# shield.net
KiCad netlist of a schematic drawn in EAGLE
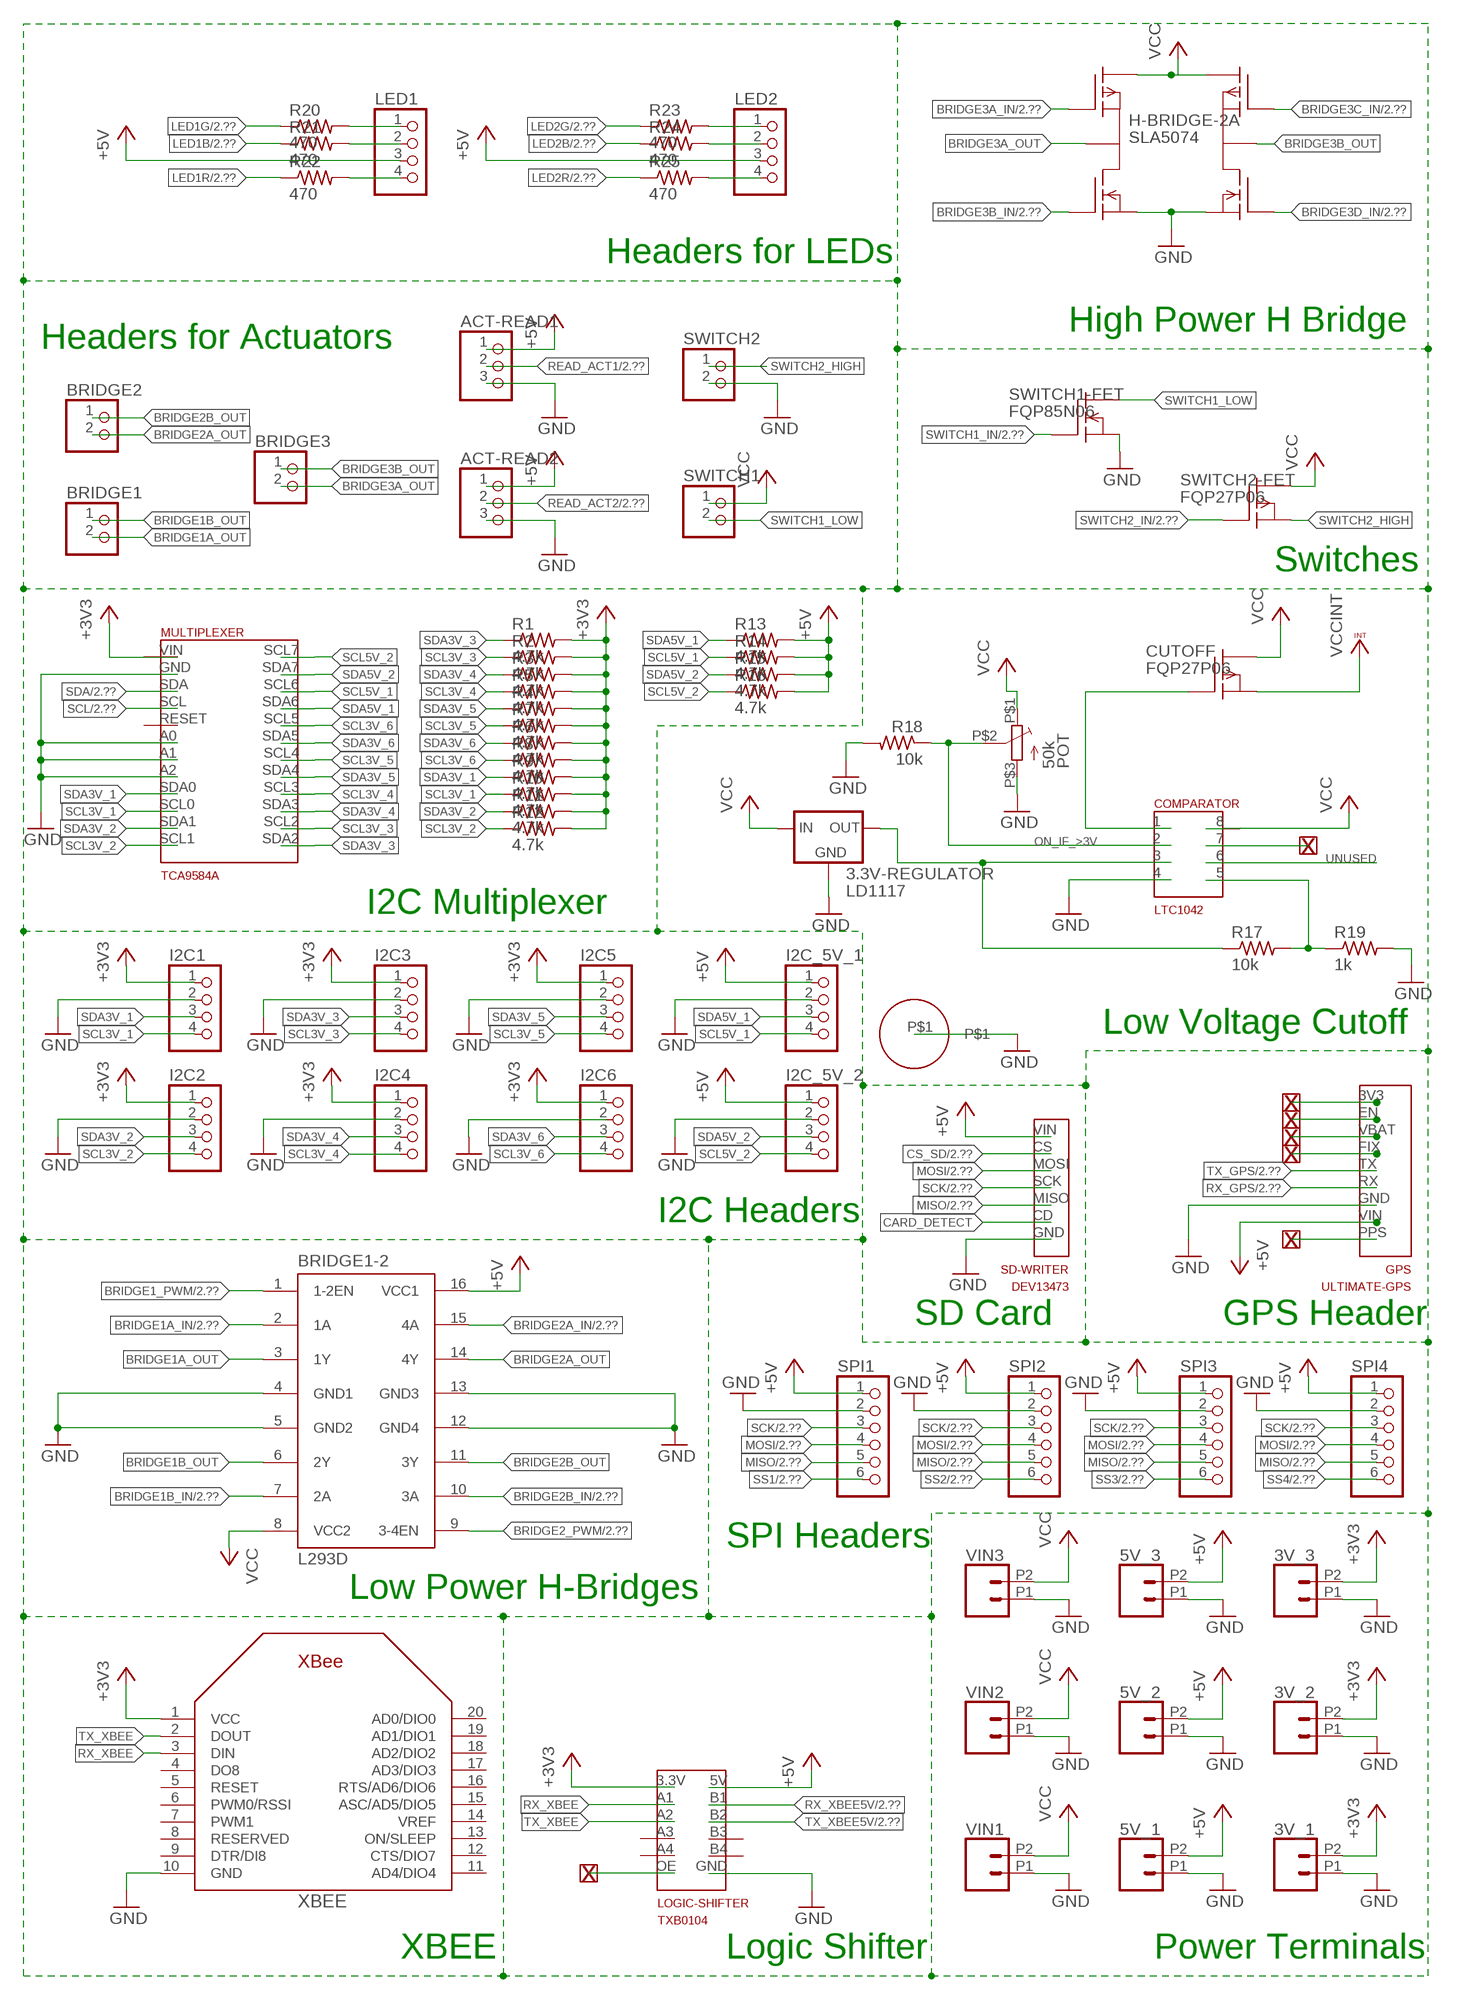
[diagram p0: schematic, sheet 1]
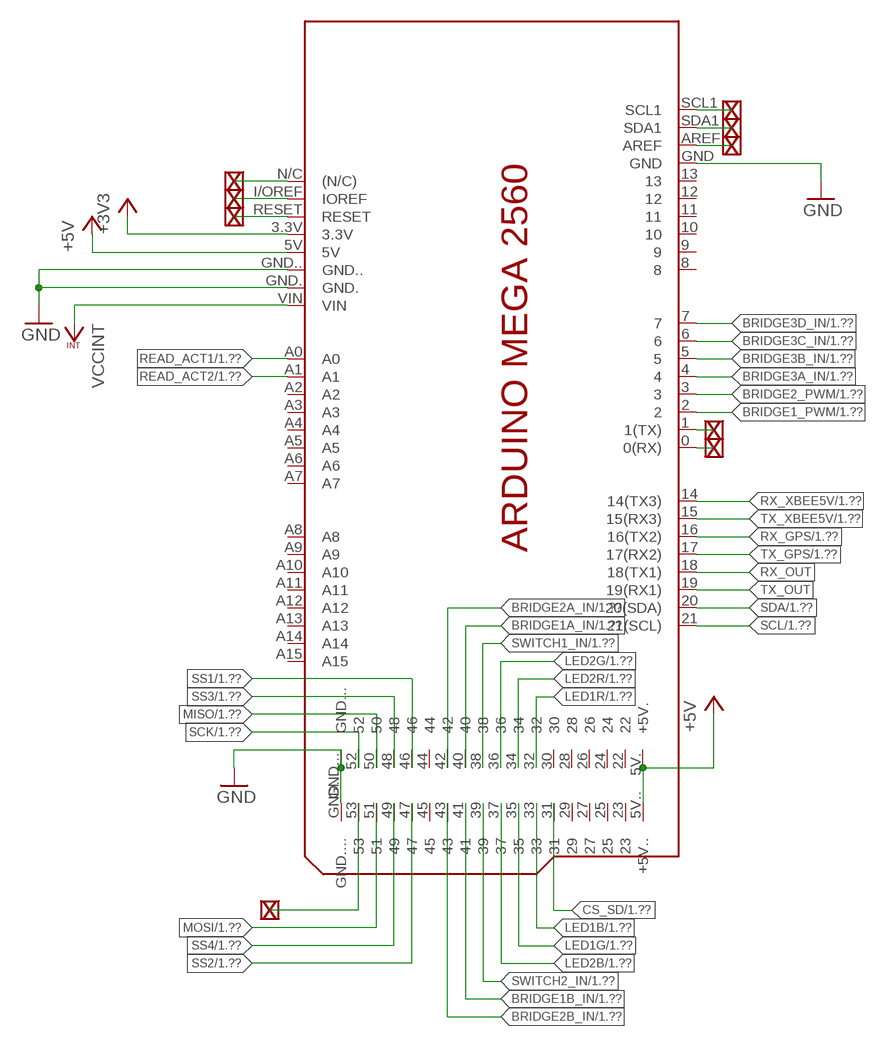
[diagram p1: schematic, sheet 2]

(export (version "E")
  (design (tool "Eeschema 10.0.6"))
  (components
    (comp (ref "PCB2")
      (value "ARDUINO_MEGA2560_SHIELD")
      (footprint "eagle-import:ARDUINO_MEGA2560_SHIELD")
      (libsource (lib "eagle-import") (part "ARDUINO_MEGA2560_SHIELD"))
    )
    (comp (ref "3.3V-REGULATOR")
      (value "LD1117")
      (footprint "eagle-import:REGULATOR")
      (libsource (lib "eagle-import") (part "LD1117"))
    )
    (comp (ref "3V_1")
      (value "CONN_022.54MM_SCREWTERM")
      (footprint "eagle-import:1X02_2.54_SCREWTERM")
      (libsource (lib "eagle-import") (part "CONN_022.54MM_SCREWTERM"))
    )
    (comp (ref "3V_2")
      (value "CONN_022.54MM_SCREWTERM")
      (footprint "eagle-import:1X02_2.54_SCREWTERM")
      (libsource (lib "eagle-import") (part "CONN_022.54MM_SCREWTERM"))
    )
    (comp (ref "3V_3")
      (value "CONN_022.54MM_SCREWTERM")
      (footprint "eagle-import:1X02_2.54_SCREWTERM")
      (libsource (lib "eagle-import") (part "CONN_022.54MM_SCREWTERM"))
    )
    (comp (ref "5V_1")
      (value "CONN_022.54MM_SCREWTERM")
      (footprint "eagle-import:1X02_2.54_SCREWTERM")
      (libsource (lib "eagle-import") (part "CONN_022.54MM_SCREWTERM"))
    )
    (comp (ref "5V_2")
      (value "CONN_022.54MM_SCREWTERM")
      (footprint "eagle-import:1X02_2.54_SCREWTERM")
      (libsource (lib "eagle-import") (part "CONN_022.54MM_SCREWTERM"))
    )
    (comp (ref "5V_3")
      (value "CONN_022.54MM_SCREWTERM")
      (footprint "eagle-import:1X02_2.54_SCREWTERM")
      (libsource (lib "eagle-import") (part "CONN_022.54MM_SCREWTERM"))
    )
    (comp (ref "ACT-READ1")
      (value "PINHD-1X3")
      (footprint "eagle-import:1X03")
      (libsource (lib "eagle-import") (part "PINHD-1X3"))
    )
    (comp (ref "ACT-READ2")
      (value "PINHD-1X3")
      (footprint "eagle-import:1X03")
      (libsource (lib "eagle-import") (part "PINHD-1X3"))
    )
    (comp (ref "BRIDGE1")
      (value "PINHD-1X2")
      (footprint "eagle-import:1X02")
      (libsource (lib "eagle-import") (part "PINHD-1X2"))
    )
    (comp (ref "BRIDGE1-2")
      (value "L293D")
      (footprint "eagle-import:DIL16")
      (libsource (lib "eagle-import") (part "L293D"))
    )
    (comp (ref "BRIDGE2")
      (value "PINHD-1X2")
      (footprint "eagle-import:1X02")
      (libsource (lib "eagle-import") (part "PINHD-1X2"))
    )
    (comp (ref "BRIDGE3")
      (value "PINHD-1X2")
      (footprint "eagle-import:1X02")
      (libsource (lib "eagle-import") (part "PINHD-1X2"))
    )
    (comp (ref "COMPARATOR")
      (value "LTC1042")
      (footprint "eagle-import:DIP8")
      (libsource (lib "eagle-import") (part "LTC1042"))
    )
    (comp (ref "CUTOFF")
      (value "FQP27P06")
      (footprint "eagle-import:MOSFET")
      (libsource (lib "eagle-import") (part "FQP27P06"))
    )
    (comp (ref "GPS")
      (value "ULTIMATE-GPS")
      (footprint "eagle-import:GPS")
      (libsource (lib "eagle-import") (part "ULTIMATE-GPS"))
    )
    (comp (ref "H-BRIDGE-2A")
      (value "SLA5074")
      (footprint "eagle-import:SANKEN")
      (libsource (lib "eagle-import") (part "SLA5074"))
    )
    (comp (ref "I2C1")
      (value "PINHD-1X4")
      (footprint "eagle-import:1X04")
      (libsource (lib "eagle-import") (part "PINHD-1X4"))
    )
    (comp (ref "I2C2")
      (value "PINHD-1X4")
      (footprint "eagle-import:1X04")
      (libsource (lib "eagle-import") (part "PINHD-1X4"))
    )
    (comp (ref "I2C3")
      (value "PINHD-1X4")
      (footprint "eagle-import:1X04")
      (libsource (lib "eagle-import") (part "PINHD-1X4"))
    )
    (comp (ref "I2C4")
      (value "PINHD-1X4")
      (footprint "eagle-import:1X04")
      (libsource (lib "eagle-import") (part "PINHD-1X4"))
    )
    (comp (ref "I2C5")
      (value "PINHD-1X4")
      (footprint "eagle-import:1X04")
      (libsource (lib "eagle-import") (part "PINHD-1X4"))
    )
    (comp (ref "I2C6")
      (value "PINHD-1X4")
      (footprint "eagle-import:1X04")
      (libsource (lib "eagle-import") (part "PINHD-1X4"))
    )
    (comp (ref "I2C_5V_1")
      (value "PINHD-1X4")
      (footprint "eagle-import:1X04")
      (libsource (lib "eagle-import") (part "PINHD-1X4"))
    )
    (comp (ref "I2C_5V_2")
      (value "PINHD-1X4")
      (footprint "eagle-import:1X04")
      (libsource (lib "eagle-import") (part "PINHD-1X4"))
    )
    (comp (ref "LED1")
      (value "PINHD-1X4")
      (footprint "eagle-import:1X04")
      (libsource (lib "eagle-import") (part "PINHD-1X4"))
    )
    (comp (ref "LED2")
      (value "PINHD-1X4")
      (footprint "eagle-import:1X04")
      (libsource (lib "eagle-import") (part "PINHD-1X4"))
    )
    (comp (ref "LOGIC-SHIFTER")
      (value "TXB0104")
      (footprint "eagle-import:TXB0104")
      (libsource (lib "eagle-import") (part "TXB0104"))
    )
    (comp (ref "MULTIPLEXER")
      (value "TCA9584A")
      (footprint "eagle-import:TCA9584A")
      (libsource (lib "eagle-import") (part "TCA9584A"))
    )
    (comp (ref "POT")
      (value "50k")
      (footprint "eagle-import:PV37W503C01B00")
      (libsource (lib "eagle-import") (part "PV37W503C01B00"))
    )
    (comp (ref "R1")
      (value "4.7k")
      (footprint "eagle-import:0805-THM")
      (libsource (lib "eagle-import") (part "R-US_FLIPFLOP"))
    )
    (comp (ref "R2")
      (value "4.7k")
      (footprint "eagle-import:0805-THM")
      (libsource (lib "eagle-import") (part "R-US_FLIPFLOP"))
    )
    (comp (ref "R3")
      (value "4.7k")
      (footprint "eagle-import:0805-THM")
      (libsource (lib "eagle-import") (part "R-US_FLIPFLOP"))
    )
    (comp (ref "R4")
      (value "4.7k")
      (footprint "eagle-import:0805-THM")
      (libsource (lib "eagle-import") (part "R-US_FLIPFLOP"))
    )
    (comp (ref "R5")
      (value "4.7k")
      (footprint "eagle-import:0805-THM")
      (libsource (lib "eagle-import") (part "R-US_FLIPFLOP"))
    )
    (comp (ref "R6")
      (value "4.7k")
      (footprint "eagle-import:0805-THM")
      (libsource (lib "eagle-import") (part "R-US_FLIPFLOP"))
    )
    (comp (ref "R7")
      (value "4.7k")
      (footprint "eagle-import:0805-THM")
      (libsource (lib "eagle-import") (part "R-US_FLIPFLOP"))
    )
    (comp (ref "R8")
      (value "4.7k")
      (footprint "eagle-import:0805-THM")
      (libsource (lib "eagle-import") (part "R-US_FLIPFLOP"))
    )
    (comp (ref "R9")
      (value "4.7k")
      (footprint "eagle-import:0805-THM")
      (libsource (lib "eagle-import") (part "R-US_FLIPFLOP"))
    )
    (comp (ref "R10")
      (value "4.7k")
      (footprint "eagle-import:0805-THM")
      (libsource (lib "eagle-import") (part "R-US_FLIPFLOP"))
    )
    (comp (ref "R11")
      (value "4.7k")
      (footprint "eagle-import:0805-THM")
      (libsource (lib "eagle-import") (part "R-US_FLIPFLOP"))
    )
    (comp (ref "R12")
      (value "4.7k")
      (footprint "eagle-import:0805-THM")
      (libsource (lib "eagle-import") (part "R-US_FLIPFLOP"))
    )
    (comp (ref "R13")
      (value "4.7k")
      (footprint "eagle-import:0805-THM")
      (libsource (lib "eagle-import") (part "R-US_FLIPFLOP"))
    )
    (comp (ref "R14")
      (value "4.7k")
      (footprint "eagle-import:0805-THM")
      (libsource (lib "eagle-import") (part "R-US_FLIPFLOP"))
    )
    (comp (ref "R15")
      (value "4.7k")
      (footprint "eagle-import:0805-THM")
      (libsource (lib "eagle-import") (part "R-US_FLIPFLOP"))
    )
    (comp (ref "R16")
      (value "4.7k")
      (footprint "eagle-import:0805-THM")
      (libsource (lib "eagle-import") (part "R-US_FLIPFLOP"))
    )
    (comp (ref "R17")
      (value "10k")
      (footprint "eagle-import:0805-THM")
      (libsource (lib "eagle-import") (part "R-US_FLIPFLOP"))
    )
    (comp (ref "R18")
      (value "10k")
      (footprint "eagle-import:0805-THM")
      (libsource (lib "eagle-import") (part "R-US_FLIPFLOP"))
    )
    (comp (ref "R19")
      (value "1k")
      (footprint "eagle-import:0805-THM")
      (libsource (lib "eagle-import") (part "R-US_FLIPFLOP"))
    )
    (comp (ref "R20")
      (value "470")
      (footprint "eagle-import:0805-THM")
      (libsource (lib "eagle-import") (part "R-US_FLIPFLOP"))
    )
    (comp (ref "R21")
      (value "470")
      (footprint "eagle-import:0805-THM")
      (libsource (lib "eagle-import") (part "R-US_FLIPFLOP"))
    )
    (comp (ref "R22")
      (value "470")
      (footprint "eagle-import:0805-THM")
      (libsource (lib "eagle-import") (part "R-US_FLIPFLOP"))
    )
    (comp (ref "R23")
      (value "470")
      (footprint "eagle-import:0805-THM")
      (libsource (lib "eagle-import") (part "R-US_FLIPFLOP"))
    )
    (comp (ref "R24")
      (value "470")
      (footprint "eagle-import:0805-THM")
      (libsource (lib "eagle-import") (part "R-US_FLIPFLOP"))
    )
    (comp (ref "R25")
      (value "470")
      (footprint "eagle-import:0805-THM")
      (libsource (lib "eagle-import") (part "R-US_FLIPFLOP"))
    )
    (comp (ref "SD-WRITER")
      (value "DEV13473")
      (footprint "eagle-import:DEV13743")
      (libsource (lib "eagle-import") (part "DEV13473"))
    )
    (comp (ref "SPI1")
      (value "PINHD-1X6")
      (footprint "eagle-import:1X06")
      (libsource (lib "eagle-import") (part "PINHD-1X6"))
    )
    (comp (ref "SPI2")
      (value "PINHD-1X6")
      (footprint "eagle-import:1X06")
      (libsource (lib "eagle-import") (part "PINHD-1X6"))
    )
    (comp (ref "SPI3")
      (value "PINHD-1X6")
      (footprint "eagle-import:1X06")
      (libsource (lib "eagle-import") (part "PINHD-1X6"))
    )
    (comp (ref "SPI4")
      (value "PINHD-1X6")
      (footprint "eagle-import:1X06")
      (libsource (lib "eagle-import") (part "PINHD-1X6"))
    )
    (comp (ref "SWITCH1")
      (value "PINHD-1X2")
      (footprint "eagle-import:1X02")
      (libsource (lib "eagle-import") (part "PINHD-1X2"))
    )
    (comp (ref "SWITCH1-FET")
      (value "FQP85N06")
      (footprint "eagle-import:MOSFET")
      (libsource (lib "eagle-import") (part "FQP85N06"))
    )
    (comp (ref "SWITCH2")
      (value "PINHD-1X2")
      (footprint "eagle-import:1X02")
      (libsource (lib "eagle-import") (part "PINHD-1X2"))
    )
    (comp (ref "SWITCH2-FET")
      (value "FQP27P06")
      (footprint "eagle-import:MOSFET")
      (libsource (lib "eagle-import") (part "FQP27P06"))
    )
    (comp (ref "U$1")
      (value "6BOLT")
      (footprint "eagle-import:6BOLT")
      (libsource (lib "eagle-import") (part "6BOLT"))
    )
    (comp (ref "VIN1")
      (value "CONN_022.54MM_SCREWTERM")
      (footprint "eagle-import:1X02_2.54_SCREWTERM")
      (libsource (lib "eagle-import") (part "CONN_022.54MM_SCREWTERM"))
    )
    (comp (ref "VIN2")
      (value "CONN_022.54MM_SCREWTERM")
      (footprint "eagle-import:1X02_2.54_SCREWTERM")
      (libsource (lib "eagle-import") (part "CONN_022.54MM_SCREWTERM"))
    )
    (comp (ref "VIN3")
      (value "CONN_022.54MM_SCREWTERM")
      (footprint "eagle-import:1X02_2.54_SCREWTERM")
      (libsource (lib "eagle-import") (part "CONN_022.54MM_SCREWTERM"))
    )
    (comp (ref "XBEE")
      (value "XBEE")
      (footprint "eagle-import:XBEE")
      (libsource (lib "eagle-import") (part "XBEE"))
    )
  )
  (nets
    (net (code "1") (name "+3V3") (class "Default")
      (node (ref "3V_1") (pin "P2") (pinfunction "2_P2") (pintype "passive"))
      (node (ref "3V_2") (pin "P2") (pinfunction "2_P2") (pintype "passive"))
      (node (ref "3V_3") (pin "P2") (pinfunction "2_P2") (pintype "passive"))
      (node (ref "I2C1") (pin "1") (pinfunction "1_1") (pintype "passive"))
      (node (ref "I2C2") (pin "1") (pinfunction "1_1") (pintype "passive"))
      (node (ref "I2C3") (pin "1") (pinfunction "1_1") (pintype "passive"))
      (node (ref "I2C4") (pin "1") (pinfunction "1_1") (pintype "passive"))
      (node (ref "I2C5") (pin "1") (pinfunction "1_1") (pintype "passive"))
      (node (ref "I2C6") (pin "1") (pinfunction "1_1") (pintype "passive"))
      (node (ref "LOGIC-SHIFTER") (pin "3.3V") (pinfunction "3V3_3.3V") (pintype "bidirectional"))
      (node (ref "MULTIPLEXER") (pin "VIN") (pinfunction "VIN_VIN") (pintype "bidirectional"))
      (node (ref "PCB2") (pin "3.3V") (pinfunction "3.3V_3.3V") (pintype "bidirectional"))
      (node (ref "R1") (pin "2") (pinfunction "2_2") (pintype "passive"))
      (node (ref "R10") (pin "2") (pinfunction "2_2") (pintype "passive"))
      (node (ref "R11") (pin "2") (pinfunction "2_2") (pintype "passive"))
      (node (ref "R12") (pin "2") (pinfunction "2_2") (pintype "passive"))
      (node (ref "R2") (pin "2") (pinfunction "2_2") (pintype "passive"))
      (node (ref "R3") (pin "2") (pinfunction "2_2") (pintype "passive"))
      (node (ref "R4") (pin "2") (pinfunction "2_2") (pintype "passive"))
      (node (ref "R5") (pin "2") (pinfunction "2_2") (pintype "passive"))
      (node (ref "R6") (pin "2") (pinfunction "2_2") (pintype "passive"))
      (node (ref "R7") (pin "2") (pinfunction "2_2") (pintype "passive"))
      (node (ref "R8") (pin "2") (pinfunction "2_2") (pintype "passive"))
      (node (ref "R9") (pin "2") (pinfunction "2_2") (pintype "passive"))
      (node (ref "XBEE") (pin "1") (pinfunction "VCC_1") (pintype "power_in"))
    )
    (net (code "2") (name "+5V") (class "Default")
      (node (ref "5V_1") (pin "P2") (pinfunction "2_P2") (pintype "passive"))
      (node (ref "5V_2") (pin "P2") (pinfunction "2_P2") (pintype "passive"))
      (node (ref "5V_3") (pin "P2") (pinfunction "2_P2") (pintype "passive"))
      (node (ref "ACT-READ1") (pin "1") (pinfunction "1_1") (pintype "passive"))
      (node (ref "ACT-READ2") (pin "1") (pinfunction "1_1") (pintype "passive"))
      (node (ref "BRIDGE1-2") (pin "16") (pinfunction "VCC1_16") (pintype "power_in"))
      (node (ref "GPS") (pin "VIN") (pinfunction "VIN_VIN") (pintype "bidirectional"))
      (node (ref "I2C_5V_1") (pin "1") (pinfunction "1_1") (pintype "passive"))
      (node (ref "I2C_5V_2") (pin "1") (pinfunction "1_1") (pintype "passive"))
      (node (ref "LED1") (pin "3") (pinfunction "3_3") (pintype "passive"))
      (node (ref "LED2") (pin "3") (pinfunction "3_3") (pintype "passive"))
      (node (ref "LOGIC-SHIFTER") (pin "5V") (pinfunction "5V_5V") (pintype "bidirectional"))
      (node (ref "PCB2") (pin "5V") (pinfunction "5V_5V") (pintype "bidirectional"))
      (node (ref "PCB2") (pin "5V.") (pinfunction "+5V._5V.") (pintype "bidirectional"))
      (node (ref "PCB2") (pin "5V..") (pinfunction "+5V.._5V..") (pintype "bidirectional"))
      (node (ref "R13") (pin "2") (pinfunction "2_2") (pintype "passive"))
      (node (ref "R14") (pin "2") (pinfunction "2_2") (pintype "passive"))
      (node (ref "R15") (pin "2") (pinfunction "2_2") (pintype "passive"))
      (node (ref "R16") (pin "2") (pinfunction "2_2") (pintype "passive"))
      (node (ref "SD-WRITER") (pin "VIN") (pinfunction "VIN_VIN") (pintype "bidirectional"))
      (node (ref "SPI1") (pin "1") (pinfunction "1_1") (pintype "passive"))
      (node (ref "SPI2") (pin "1") (pinfunction "1_1") (pintype "passive"))
      (node (ref "SPI3") (pin "1") (pinfunction "1_1") (pintype "passive"))
      (node (ref "SPI4") (pin "1") (pinfunction "1_1") (pintype "passive"))
    )
    (net (code "3") (name "BRIDGE1A_IN") (class "Default")
      (node (ref "BRIDGE1-2") (pin "2") (pinfunction "1A_2") (pintype "input"))
      (node (ref "PCB2") (pin "40") (pinfunction "40_40") (pintype "bidirectional"))
    )
    (net (code "4") (name "BRIDGE1A_OUT") (class "Default")
      (node (ref "BRIDGE1") (pin "2") (pinfunction "2_2") (pintype "passive"))
      (node (ref "BRIDGE1-2") (pin "3") (pinfunction "1Y_3") (pintype "output"))
    )
    (net (code "5") (name "BRIDGE1B_IN") (class "Default")
      (node (ref "BRIDGE1-2") (pin "7") (pinfunction "2A_7") (pintype "input"))
      (node (ref "PCB2") (pin "41") (pinfunction "41_41") (pintype "bidirectional"))
    )
    (net (code "6") (name "BRIDGE1B_OUT") (class "Default")
      (node (ref "BRIDGE1") (pin "1") (pinfunction "1_1") (pintype "passive"))
      (node (ref "BRIDGE1-2") (pin "6") (pinfunction "2Y_6") (pintype "output"))
    )
    (net (code "7") (name "BRIDGE1_PWM") (class "Default")
      (node (ref "BRIDGE1-2") (pin "1") (pinfunction "1-2EN_1") (pintype "input"))
      (node (ref "PCB2") (pin "2") (pinfunction "2_2") (pintype "bidirectional"))
    )
    (net (code "8") (name "BRIDGE2A_IN") (class "Default")
      (node (ref "BRIDGE1-2") (pin "15") (pinfunction "4A_15") (pintype "input"))
      (node (ref "PCB2") (pin "42") (pinfunction "42_42") (pintype "bidirectional"))
    )
    (net (code "9") (name "BRIDGE2A_OUT") (class "Default")
      (node (ref "BRIDGE1-2") (pin "14") (pinfunction "4Y_14") (pintype "output"))
      (node (ref "BRIDGE2") (pin "2") (pinfunction "2_2") (pintype "passive"))
    )
    (net (code "10") (name "BRIDGE2B_IN") (class "Default")
      (node (ref "BRIDGE1-2") (pin "10") (pinfunction "3A_10") (pintype "input"))
      (node (ref "PCB2") (pin "43") (pinfunction "43_43") (pintype "bidirectional"))
    )
    (net (code "11") (name "BRIDGE2B_OUT") (class "Default")
      (node (ref "BRIDGE1-2") (pin "11") (pinfunction "3Y_11") (pintype "output"))
      (node (ref "BRIDGE2") (pin "1") (pinfunction "1_1") (pintype "passive"))
    )
    (net (code "12") (name "BRIDGE2_PWM") (class "Default")
      (node (ref "BRIDGE1-2") (pin "9") (pinfunction "3-4EN_9") (pintype "input"))
      (node (ref "PCB2") (pin "3") (pinfunction "3_3") (pintype "bidirectional"))
    )
    (net (code "13") (name "BRIDGE3A_IN") (class "Default")
      (node (ref "H-BRIDGE-2A") (pin "P$4") (pinfunction "P$4_P$4") (pintype "passive"))
      (node (ref "PCB2") (pin "4") (pinfunction "4_4") (pintype "bidirectional"))
    )
    (net (code "14") (name "BRIDGE3A_OUT") (class "Default")
      (node (ref "BRIDGE3") (pin "2") (pinfunction "2_2") (pintype "passive"))
      (node (ref "H-BRIDGE-2A") (pin "P$3") (pinfunction "P$3_P$3") (pintype "passive"))
    )
    (net (code "15") (name "BRIDGE3B_IN") (class "Default")
      (node (ref "H-BRIDGE-2A") (pin "P$2") (pinfunction "P$2_P$2") (pintype "passive"))
      (node (ref "PCB2") (pin "5") (pinfunction "5_5") (pintype "bidirectional"))
    )
    (net (code "16") (name "BRIDGE3B_OUT") (class "Default")
      (node (ref "BRIDGE3") (pin "1") (pinfunction "1_1") (pintype "passive"))
      (node (ref "H-BRIDGE-2A") (pin "P$7") (pinfunction "P$7_P$7") (pintype "passive"))
    )
    (net (code "17") (name "BRIDGE3C_IN") (class "Default")
      (node (ref "H-BRIDGE-2A") (pin "P$9") (pinfunction "P$9_P$9") (pintype "passive"))
      (node (ref "PCB2") (pin "6") (pinfunction "6_6") (pintype "bidirectional"))
    )
    (net (code "18") (name "BRIDGE3D_IN") (class "Default")
      (node (ref "H-BRIDGE-2A") (pin "P$6") (pinfunction "P$6_P$6") (pintype "passive"))
      (node (ref "PCB2") (pin "7") (pinfunction "7_7") (pintype "bidirectional"))
    )
    (net (code "19") (name "CARD_DETECT") (class "Default")
      (node (ref "SD-WRITER") (pin "CD") (pinfunction "CD_CD") (pintype "bidirectional"))
    )
    (net (code "20") (name "CS_SD") (class "Default")
      (node (ref "PCB2") (pin "31") (pinfunction "31_31") (pintype "bidirectional"))
      (node (ref "SD-WRITER") (pin "CS") (pinfunction "CS_CS") (pintype "bidirectional"))
    )
    (net (code "21") (name "GND") (class "Default")
      (node (ref "3.3V-REGULATOR") (pin "GND") (pinfunction "GND_GND") (pintype "input"))
      (node (ref "3V_1") (pin "P1") (pinfunction "1_P1") (pintype "passive"))
      (node (ref "3V_2") (pin "P1") (pinfunction "1_P1") (pintype "passive"))
      (node (ref "3V_3") (pin "P1") (pinfunction "1_P1") (pintype "passive"))
      (node (ref "5V_1") (pin "P1") (pinfunction "1_P1") (pintype "passive"))
      (node (ref "5V_2") (pin "P1") (pinfunction "1_P1") (pintype "passive"))
      (node (ref "5V_3") (pin "P1") (pinfunction "1_P1") (pintype "passive"))
      (node (ref "ACT-READ1") (pin "3") (pinfunction "3_3") (pintype "passive"))
      (node (ref "ACT-READ2") (pin "3") (pinfunction "3_3") (pintype "passive"))
      (node (ref "BRIDGE1-2") (pin "12") (pinfunction "GND4_12") (pintype "power_in"))
      (node (ref "BRIDGE1-2") (pin "13") (pinfunction "GND3_13") (pintype "power_in"))
      (node (ref "BRIDGE1-2") (pin "4") (pinfunction "GND1_4") (pintype "power_in"))
      (node (ref "BRIDGE1-2") (pin "5") (pinfunction "GND2_5") (pintype "power_in"))
      (node (ref "COMPARATOR") (pin "4") (pinfunction "GND_4") (pintype "bidirectional"))
      (node (ref "GPS") (pin "GND") (pinfunction "GND_GND") (pintype "bidirectional"))
      (node (ref "H-BRIDGE-2A") (pin "P$1") (pinfunction "P$1_P$1") (pintype "passive"))
      (node (ref "H-BRIDGE-2A") (pin "P$8") (pinfunction "P$8_P$8") (pintype "passive"))
      (node (ref "I2C1") (pin "2") (pinfunction "2_2") (pintype "passive"))
      (node (ref "I2C2") (pin "2") (pinfunction "2_2") (pintype "passive"))
      (node (ref "I2C3") (pin "2") (pinfunction "2_2") (pintype "passive"))
      (node (ref "I2C4") (pin "2") (pinfunction "2_2") (pintype "passive"))
      (node (ref "I2C5") (pin "2") (pinfunction "2_2") (pintype "passive"))
      (node (ref "I2C6") (pin "2") (pinfunction "2_2") (pintype "passive"))
      (node (ref "I2C_5V_1") (pin "2") (pinfunction "2_2") (pintype "passive"))
      (node (ref "I2C_5V_2") (pin "2") (pinfunction "2_2") (pintype "passive"))
      (node (ref "LOGIC-SHIFTER") (pin "GND") (pinfunction "GND_GND") (pintype "bidirectional"))
      (node (ref "MULTIPLEXER") (pin "A0") (pinfunction "A0_A0") (pintype "bidirectional"))
      (node (ref "MULTIPLEXER") (pin "A1") (pinfunction "A1_A1") (pintype "bidirectional"))
      (node (ref "MULTIPLEXER") (pin "A2") (pinfunction "A2_A2") (pintype "bidirectional"))
      (node (ref "MULTIPLEXER") (pin "GND") (pinfunction "GND_GND") (pintype "bidirectional"))
      (node (ref "PCB2") (pin "GND") (pinfunction "GND_GND") (pintype "bidirectional"))
      (node (ref "PCB2") (pin "GND.") (pinfunction "GND._GND.") (pintype "bidirectional"))
      (node (ref "PCB2") (pin "GND..") (pinfunction "GND.._GND..") (pintype "bidirectional"))
      (node (ref "PCB2") (pin "GND...") (pinfunction "GND..._GND...") (pintype "bidirectional"))
      (node (ref "PCB2") (pin "GND....") (pinfunction "GND...._GND....") (pintype "bidirectional"))
      (node (ref "POT") (pin "P$3") (pinfunction "P$3_P$3") (pintype "passive"))
      (node (ref "R18") (pin "2") (pinfunction "2_2") (pintype "passive"))
      (node (ref "R19") (pin "2") (pinfunction "2_2") (pintype "passive"))
      (node (ref "SD-WRITER") (pin "GND") (pinfunction "GND_GND") (pintype "bidirectional"))
      (node (ref "SPI1") (pin "2") (pinfunction "2_2") (pintype "passive"))
      (node (ref "SPI2") (pin "2") (pinfunction "2_2") (pintype "passive"))
      (node (ref "SPI3") (pin "2") (pinfunction "2_2") (pintype "passive"))
      (node (ref "SPI4") (pin "2") (pinfunction "2_2") (pintype "passive"))
      (node (ref "SWITCH1-FET") (pin "S") (pinfunction "S_S") (pintype "passive"))
      (node (ref "SWITCH2") (pin "2") (pinfunction "2_2") (pintype "passive"))
      (node (ref "U$1") (pin "P$1") (pinfunction "P$1_P$1") (pintype "bidirectional"))
      (node (ref "VIN1") (pin "P1") (pinfunction "1_P1") (pintype "passive"))
      (node (ref "VIN2") (pin "P1") (pinfunction "1_P1") (pintype "passive"))
      (node (ref "VIN3") (pin "P1") (pinfunction "1_P1") (pintype "passive"))
      (node (ref "XBEE") (pin "10") (pinfunction "GND_10") (pintype "power_in"))
    )
    (net (code "22") (name "LED1B") (class "Default")
      (node (ref "PCB2") (pin "33") (pinfunction "33_33") (pintype "bidirectional"))
      (node (ref "R21") (pin "1") (pinfunction "1_1") (pintype "passive"))
    )
    (net (code "23") (name "LED1G") (class "Default")
      (node (ref "PCB2") (pin "35") (pinfunction "35_35") (pintype "bidirectional"))
      (node (ref "R20") (pin "1") (pinfunction "1_1") (pintype "passive"))
    )
    (net (code "24") (name "LED1R") (class "Default")
      (node (ref "PCB2") (pin "32") (pinfunction "32_32") (pintype "bidirectional"))
      (node (ref "R22") (pin "1") (pinfunction "1_1") (pintype "passive"))
    )
    (net (code "25") (name "LED2B") (class "Default")
      (node (ref "PCB2") (pin "37") (pinfunction "37_37") (pintype "bidirectional"))
      (node (ref "R24") (pin "1") (pinfunction "1_1") (pintype "passive"))
    )
    (net (code "26") (name "LED2G") (class "Default")
      (node (ref "PCB2") (pin "36") (pinfunction "36_36") (pintype "bidirectional"))
      (node (ref "R23") (pin "1") (pinfunction "1_1") (pintype "passive"))
    )
    (net (code "27") (name "LED2R") (class "Default")
      (node (ref "PCB2") (pin "34") (pinfunction "34_34") (pintype "bidirectional"))
      (node (ref "R25") (pin "1") (pinfunction "1_1") (pintype "passive"))
    )
    (net (code "28") (name "MISO") (class "Default")
      (node (ref "PCB2") (pin "50") (pinfunction "50_50") (pintype "bidirectional"))
      (node (ref "SD-WRITER") (pin "MISO") (pinfunction "MISO_MISO") (pintype "bidirectional"))
      (node (ref "SPI1") (pin "5") (pinfunction "5_5") (pintype "passive"))
      (node (ref "SPI2") (pin "5") (pinfunction "5_5") (pintype "passive"))
      (node (ref "SPI3") (pin "5") (pinfunction "5_5") (pintype "passive"))
      (node (ref "SPI4") (pin "5") (pinfunction "5_5") (pintype "passive"))
    )
    (net (code "29") (name "MOSI") (class "Default")
      (node (ref "PCB2") (pin "51") (pinfunction "51_51") (pintype "bidirectional"))
      (node (ref "SD-WRITER") (pin "MOSI") (pinfunction "MOSI_MOSI") (pintype "bidirectional"))
      (node (ref "SPI1") (pin "4") (pinfunction "4_4") (pintype "passive"))
      (node (ref "SPI2") (pin "4") (pinfunction "4_4") (pintype "passive"))
      (node (ref "SPI3") (pin "4") (pinfunction "4_4") (pintype "passive"))
      (node (ref "SPI4") (pin "4") (pinfunction "4_4") (pintype "passive"))
    )
    (net (code "30") (name "Net-(COMPARATOR-VIN)") (class "Default")
      (node (ref "3.3V-REGULATOR") (pin "VOUT") (pinfunction "VOUT_VOUT") (pintype "passive"))
      (node (ref "COMPARATOR") (pin "3") (pinfunction "VIN_3") (pintype "bidirectional"))
      (node (ref "R17") (pin "1") (pinfunction "1_1") (pintype "passive"))
    )
    (net (code "31") (name "Net-(COMPARATOR-WIDTH{slash}2)") (class "Default")
      (node (ref "COMPARATOR") (pin "5") (pinfunction "WIDTH/2_5") (pintype "bidirectional"))
      (node (ref "R17") (pin "2") (pinfunction "2_2") (pintype "passive"))
      (node (ref "R19") (pin "1") (pinfunction "1_1") (pintype "passive"))
    )
    (net (code "32") (name "Net-(COMPARATOR-WITHIN-WINDOW)") (class "Default")
      (node (ref "COMPARATOR") (pin "1") (pinfunction "WITHIN-WINDOW_1") (pintype "bidirectional"))
      (node (ref "CUTOFF") (pin "G") (pinfunction "G_G") (pintype "passive"))
    )
    (net (code "33") (name "Net-(LED1-Pad1)") (class "Default")
      (node (ref "LED1") (pin "1") (pinfunction "1_1") (pintype "passive"))
      (node (ref "R20") (pin "2") (pinfunction "2_2") (pintype "passive"))
    )
    (net (code "34") (name "Net-(LED1-Pad2)") (class "Default")
      (node (ref "LED1") (pin "2") (pinfunction "2_2") (pintype "passive"))
      (node (ref "R21") (pin "2") (pinfunction "2_2") (pintype "passive"))
    )
    (net (code "35") (name "Net-(LED1-Pad4)") (class "Default")
      (node (ref "LED1") (pin "4") (pinfunction "4_4") (pintype "passive"))
      (node (ref "R22") (pin "2") (pinfunction "2_2") (pintype "passive"))
    )
    (net (code "36") (name "Net-(LED2-Pad1)") (class "Default")
      (node (ref "LED2") (pin "1") (pinfunction "1_1") (pintype "passive"))
      (node (ref "R23") (pin "2") (pinfunction "2_2") (pintype "passive"))
    )
    (net (code "37") (name "Net-(LED2-Pad2)") (class "Default")
      (node (ref "LED2") (pin "2") (pinfunction "2_2") (pintype "passive"))
      (node (ref "R24") (pin "2") (pinfunction "2_2") (pintype "passive"))
    )
    (net (code "38") (name "Net-(LED2-Pad4)") (class "Default")
      (node (ref "LED2") (pin "4") (pinfunction "4_4") (pintype "passive"))
      (node (ref "R25") (pin "2") (pinfunction "2_2") (pintype "passive"))
    )
    (net (code "39") (name "ON_IF_>3V") (class "Default")
      (node (ref "COMPARATOR") (pin "2") (pinfunction "CENTER_2") (pintype "bidirectional"))
      (node (ref "POT") (pin "P$2") (pinfunction "P$2_P$2") (pintype "passive"))
      (node (ref "R18") (pin "1") (pinfunction "1_1") (pintype "passive"))
    )
    (net (code "40") (name "READ_ACT1") (class "Default")
      (node (ref "ACT-READ1") (pin "2") (pinfunction "2_2") (pintype "passive"))
      (node (ref "PCB2") (pin "A0") (pinfunction "A0_A0") (pintype "bidirectional"))
    )
    (net (code "41") (name "READ_ACT2") (class "Default")
      (node (ref "ACT-READ2") (pin "2") (pinfunction "2_2") (pintype "passive"))
      (node (ref "PCB2") (pin "A1") (pinfunction "A1_A1") (pintype "bidirectional"))
    )
    (net (code "42") (name "RX_GPS") (class "Default")
      (node (ref "GPS") (pin "RX") (pinfunction "RX_RX") (pintype "bidirectional"))
      (node (ref "PCB2") (pin "16") (pinfunction "16(TX2)_16") (pintype "bidirectional"))
    )
    (net (code "43") (name "RX_OUT") (class "Default")
      (node (ref "PCB2") (pin "18") (pinfunction "18(TX1)_18") (pintype "bidirectional"))
    )
    (net (code "44") (name "RX_XBEE") (class "Default")
      (node (ref "LOGIC-SHIFTER") (pin "A1") (pinfunction "A1_A1") (pintype "bidirectional"))
      (node (ref "XBEE") (pin "3") (pinfunction "DIN_3") (pintype "input"))
    )
    (net (code "45") (name "RX_XBEE5V") (class "Default")
      (node (ref "LOGIC-SHIFTER") (pin "B1") (pinfunction "B1_B1") (pintype "bidirectional"))
      (node (ref "PCB2") (pin "14") (pinfunction "14(TX3)_14") (pintype "bidirectional"))
    )
    (net (code "46") (name "SCK") (class "Default")
      (node (ref "PCB2") (pin "52") (pinfunction "52_52") (pintype "bidirectional"))
      (node (ref "SD-WRITER") (pin "SCK") (pinfunction "SCK_SCK") (pintype "bidirectional"))
      (node (ref "SPI1") (pin "3") (pinfunction "3_3") (pintype "passive"))
      (node (ref "SPI2") (pin "3") (pinfunction "3_3") (pintype "passive"))
      (node (ref "SPI3") (pin "3") (pinfunction "3_3") (pintype "passive"))
      (node (ref "SPI4") (pin "3") (pinfunction "3_3") (pintype "passive"))
    )
    (net (code "47") (name "SCL") (class "Default")
      (node (ref "MULTIPLEXER") (pin "SCL") (pinfunction "SCL_SCL") (pintype "bidirectional"))
      (node (ref "PCB2") (pin "21") (pinfunction "21(SCL)_21") (pintype "bidirectional"))
    )
    (net (code "48") (name "SCL3V_1") (class "Default")
      (node (ref "I2C1") (pin "4") (pinfunction "4_4") (pintype "passive"))
      (node (ref "MULTIPLEXER") (pin "SCL0") (pinfunction "SCL0_SCL0") (pintype "bidirectional"))
      (node (ref "R10") (pin "1") (pinfunction "1_1") (pintype "passive"))
    )
    (net (code "49") (name "SCL3V_2") (class "Default")
      (node (ref "I2C2") (pin "4") (pinfunction "4_4") (pintype "passive"))
      (node (ref "MULTIPLEXER") (pin "SCL1") (pinfunction "SCL1_SCL1") (pintype "bidirectional"))
      (node (ref "R12") (pin "1") (pinfunction "1_1") (pintype "passive"))
    )
    (net (code "50") (name "SCL3V_3") (class "Default")
      (node (ref "I2C3") (pin "4") (pinfunction "4_4") (pintype "passive"))
      (node (ref "MULTIPLEXER") (pin "SCL2") (pinfunction "SCL2_SCL2") (pintype "bidirectional"))
      (node (ref "R2") (pin "1") (pinfunction "1_1") (pintype "passive"))
    )
    (net (code "51") (name "SCL3V_4") (class "Default")
      (node (ref "I2C4") (pin "4") (pinfunction "4_4") (pintype "passive"))
      (node (ref "MULTIPLEXER") (pin "SCL3") (pinfunction "SCL3_SCL3") (pintype "bidirectional"))
      (node (ref "R5") (pin "1") (pinfunction "1_1") (pintype "passive"))
    )
    (net (code "52") (name "SCL3V_5") (class "Default")
      (node (ref "I2C5") (pin "4") (pinfunction "4_4") (pintype "passive"))
      (node (ref "MULTIPLEXER") (pin "SCL4") (pinfunction "SCL4_SCL4") (pintype "bidirectional"))
      (node (ref "R7") (pin "1") (pinfunction "1_1") (pintype "passive"))
    )
    (net (code "53") (name "SCL3V_6") (class "Default")
      (node (ref "I2C6") (pin "4") (pinfunction "4_4") (pintype "passive"))
      (node (ref "MULTIPLEXER") (pin "SCL5") (pinfunction "SCL5_SCL5") (pintype "bidirectional"))
      (node (ref "R8") (pin "1") (pinfunction "1_1") (pintype "passive"))
    )
    (net (code "54") (name "SCL5V_1") (class "Default")
      (node (ref "I2C_5V_1") (pin "4") (pinfunction "4_4") (pintype "passive"))
      (node (ref "MULTIPLEXER") (pin "SCL6") (pinfunction "SCL6_SCL6") (pintype "bidirectional"))
      (node (ref "R14") (pin "1") (pinfunction "1_1") (pintype "passive"))
    )
    (net (code "55") (name "SCL5V_2") (class "Default")
      (node (ref "I2C_5V_2") (pin "4") (pinfunction "4_4") (pintype "passive"))
      (node (ref "MULTIPLEXER") (pin "SCL7") (pinfunction "SCL7_SCL7") (pintype "bidirectional"))
      (node (ref "R16") (pin "1") (pinfunction "1_1") (pintype "passive"))
    )
    (net (code "56") (name "SDA") (class "Default")
      (node (ref "MULTIPLEXER") (pin "SDA") (pinfunction "SDA_SDA") (pintype "bidirectional"))
      (node (ref "PCB2") (pin "20") (pinfunction "20(SDA)_20") (pintype "bidirectional"))
    )
    (net (code "57") (name "SDA3V_1") (class "Default")
      (node (ref "I2C1") (pin "3") (pinfunction "3_3") (pintype "passive"))
      (node (ref "MULTIPLEXER") (pin "SDA0") (pinfunction "SDA0_SDA0") (pintype "bidirectional"))
      (node (ref "R9") (pin "1") (pinfunction "1_1") (pintype "passive"))
    )
    (net (code "58") (name "SDA3V_2") (class "Default")
      (node (ref "I2C2") (pin "3") (pinfunction "3_3") (pintype "passive"))
      (node (ref "MULTIPLEXER") (pin "SDA1") (pinfunction "SDA1_SDA1") (pintype "bidirectional"))
      (node (ref "R11") (pin "1") (pinfunction "1_1") (pintype "passive"))
    )
    (net (code "59") (name "SDA3V_3") (class "Default")
      (node (ref "I2C3") (pin "3") (pinfunction "3_3") (pintype "passive"))
      (node (ref "MULTIPLEXER") (pin "SDA2") (pinfunction "SDA2_SDA2") (pintype "bidirectional"))
      (node (ref "R1") (pin "1") (pinfunction "1_1") (pintype "passive"))
    )
    (net (code "60") (name "SDA3V_4") (class "Default")
      (node (ref "I2C4") (pin "3") (pinfunction "3_3") (pintype "passive"))
      (node (ref "MULTIPLEXER") (pin "SDA3") (pinfunction "SDA3_SDA3") (pintype "bidirectional"))
      (node (ref "R3") (pin "1") (pinfunction "1_1") (pintype "passive"))
    )
    (net (code "61") (name "SDA3V_5") (class "Default")
      (node (ref "I2C5") (pin "3") (pinfunction "3_3") (pintype "passive"))
      (node (ref "MULTIPLEXER") (pin "SDA4") (pinfunction "SDA4_SDA4") (pintype "bidirectional"))
      (node (ref "R4") (pin "1") (pinfunction "1_1") (pintype "passive"))
    )
    (net (code "62") (name "SDA3V_6") (class "Default")
      (node (ref "I2C6") (pin "3") (pinfunction "3_3") (pintype "passive"))
      (node (ref "MULTIPLEXER") (pin "SDA5") (pinfunction "SDA5_SDA5") (pintype "bidirectional"))
      (node (ref "R6") (pin "1") (pinfunction "1_1") (pintype "passive"))
    )
    (net (code "63") (name "SDA5V_1") (class "Default")
      (node (ref "I2C_5V_1") (pin "3") (pinfunction "3_3") (pintype "passive"))
      (node (ref "MULTIPLEXER") (pin "SDA6") (pinfunction "SDA6_SDA6") (pintype "bidirectional"))
      (node (ref "R13") (pin "1") (pinfunction "1_1") (pintype "passive"))
    )
    (net (code "64") (name "SDA5V_2") (class "Default")
      (node (ref "I2C_5V_2") (pin "3") (pinfunction "3_3") (pintype "passive"))
      (node (ref "MULTIPLEXER") (pin "SDA7") (pinfunction "SDA7_SDA7") (pintype "bidirectional"))
      (node (ref "R15") (pin "1") (pinfunction "1_1") (pintype "passive"))
    )
    (net (code "65") (name "SS1") (class "Default")
      (node (ref "PCB2") (pin "46") (pinfunction "46_46") (pintype "bidirectional"))
      (node (ref "SPI1") (pin "6") (pinfunction "6_6") (pintype "passive"))
    )
    (net (code "66") (name "SS2") (class "Default")
      (node (ref "PCB2") (pin "47") (pinfunction "47_47") (pintype "bidirectional"))
      (node (ref "SPI2") (pin "6") (pinfunction "6_6") (pintype "passive"))
    )
    (net (code "67") (name "SS3") (class "Default")
      (node (ref "PCB2") (pin "48") (pinfunction "48_48") (pintype "bidirectional"))
      (node (ref "SPI3") (pin "6") (pinfunction "6_6") (pintype "passive"))
    )
    (net (code "68") (name "SS4") (class "Default")
      (node (ref "PCB2") (pin "49") (pinfunction "49_49") (pintype "bidirectional"))
      (node (ref "SPI4") (pin "6") (pinfunction "6_6") (pintype "passive"))
    )
    (net (code "69") (name "SWITCH1_IN") (class "Default")
      (node (ref "PCB2") (pin "38") (pinfunction "38_38") (pintype "bidirectional"))
      (node (ref "SWITCH1-FET") (pin "G") (pinfunction "G_G") (pintype "passive"))
    )
    (net (code "70") (name "SWITCH1_LOW") (class "Default")
      (node (ref "SWITCH1") (pin "2") (pinfunction "2_2") (pintype "passive"))
      (node (ref "SWITCH1-FET") (pin "D") (pinfunction "D_D") (pintype "passive"))
    )
    (net (code "71") (name "SWITCH2_HIGH") (class "Default")
      (node (ref "SWITCH2") (pin "1") (pinfunction "1_1") (pintype "passive"))
      (node (ref "SWITCH2-FET") (pin "S") (pinfunction "S_S") (pintype "passive"))
    )
    (net (code "72") (name "SWITCH2_IN") (class "Default")
      (node (ref "PCB2") (pin "39") (pinfunction "39_39") (pintype "bidirectional"))
      (node (ref "SWITCH2-FET") (pin "G") (pinfunction "G_G") (pintype "passive"))
    )
    (net (code "73") (name "TX_GPS") (class "Default")
      (node (ref "GPS") (pin "TX") (pinfunction "TX_TX") (pintype "bidirectional"))
      (node (ref "PCB2") (pin "17") (pinfunction "17(RX2)_17") (pintype "bidirectional"))
    )
    (net (code "74") (name "TX_OUT") (class "Default")
      (node (ref "PCB2") (pin "19") (pinfunction "19(RX1)_19") (pintype "bidirectional"))
    )
    (net (code "75") (name "TX_XBEE") (class "Default")
      (node (ref "LOGIC-SHIFTER") (pin "A2") (pinfunction "A2_A2") (pintype "bidirectional"))
      (node (ref "XBEE") (pin "2") (pinfunction "DOUT_2") (pintype "output"))
    )
    (net (code "76") (name "TX_XBEE5V") (class "Default")
      (node (ref "LOGIC-SHIFTER") (pin "B2") (pinfunction "B2_B2") (pintype "bidirectional"))
      (node (ref "PCB2") (pin "15") (pinfunction "15(RX3)_15") (pintype "bidirectional"))
    )
    (net (code "77") (name "UNUSED") (class "Default")
      (node (ref "COMPARATOR") (pin "6") (pinfunction "ABOVE-WINDOW_6") (pintype "bidirectional"))
    )
    (net (code "78") (name "VCC") (class "Default")
      (node (ref "3.3V-REGULATOR") (pin "VIN") (pinfunction "VIN_VIN") (pintype "input"))
      (node (ref "BRIDGE1-2") (pin "8") (pinfunction "VCC2_8") (pintype "power_in"))
      (node (ref "COMPARATOR") (pin "8") (pinfunction "V+_8") (pintype "bidirectional"))
      (node (ref "CUTOFF") (pin "D") (pinfunction "D_D") (pintype "passive"))
      (node (ref "H-BRIDGE-2A") (pin "P$10") (pinfunction "P$10_P$10") (pintype "passive"))
      (node (ref "H-BRIDGE-2A") (pin "P$5") (pinfunction "P$5_P$5") (pintype "passive"))
      (node (ref "POT") (pin "P$1") (pinfunction "P$1_P$1") (pintype "passive"))
      (node (ref "SWITCH1") (pin "1") (pinfunction "1_1") (pintype "passive"))
      (node (ref "SWITCH2-FET") (pin "D") (pinfunction "D_D") (pintype "passive"))
      (node (ref "VIN1") (pin "P2") (pinfunction "2_P2") (pintype "passive"))
      (node (ref "VIN2") (pin "P2") (pinfunction "2_P2") (pintype "passive"))
      (node (ref "VIN3") (pin "P2") (pinfunction "2_P2") (pintype "passive"))
    )
    (net (code "79") (name "VCCINT") (class "Default")
      (node (ref "CUTOFF") (pin "S") (pinfunction "S_S") (pintype "passive"))
      (node (ref "PCB2") (pin "VIN") (pinfunction "VIN_VIN") (pintype "bidirectional"))
    )
    (net (code "80") (name "unconnected-(COMPARATOR-OSC-Pad7)") (class "Default")
      (node (ref "COMPARATOR") (pin "7") (pinfunction "OSC_7") (pintype "bidirectional"))
    )
    (net (code "81") (name "unconnected-(GPS-Pad3V3)") (class "Default")
      (node (ref "GPS") (pin "3V3") (pinfunction "3V3_3V3") (pintype "bidirectional"))
    )
    (net (code "82") (name "unconnected-(GPS-PadEN)") (class "Default")
      (node (ref "GPS") (pin "EN") (pinfunction "EN_EN") (pintype "bidirectional"))
    )
    (net (code "83") (name "unconnected-(GPS-PadFIX)") (class "Default")
      (node (ref "GPS") (pin "FIX") (pinfunction "FIX_FIX") (pintype "bidirectional"))
    )
    (net (code "84") (name "unconnected-(GPS-PadPPS)") (class "Default")
      (node (ref "GPS") (pin "PPS") (pinfunction "PPS_PPS") (pintype "bidirectional"))
    )
    (net (code "85") (name "unconnected-(GPS-PadVBAT)") (class "Default")
      (node (ref "GPS") (pin "VBAT") (pinfunction "VBAT_VBAT") (pintype "bidirectional"))
    )
    (net (code "86") (name "unconnected-(LOGIC-SHIFTER-PadA3)") (class "Default")
      (node (ref "LOGIC-SHIFTER") (pin "A3") (pinfunction "A3_A3") (pintype "bidirectional"))
    )
    (net (code "87") (name "unconnected-(LOGIC-SHIFTER-PadA4)") (class "Default")
      (node (ref "LOGIC-SHIFTER") (pin "A4") (pinfunction "A4_A4") (pintype "bidirectional"))
    )
    (net (code "88") (name "unconnected-(LOGIC-SHIFTER-PadB3)") (class "Default")
      (node (ref "LOGIC-SHIFTER") (pin "B3") (pinfunction "B3_B3") (pintype "bidirectional"))
    )
    (net (code "89") (name "unconnected-(LOGIC-SHIFTER-PadB4)") (class "Default")
      (node (ref "LOGIC-SHIFTER") (pin "B4") (pinfunction "B4_B4") (pintype "bidirectional"))
    )
    (net (code "90") (name "unconnected-(LOGIC-SHIFTER-PadOE)") (class "Default")
      (node (ref "LOGIC-SHIFTER") (pin "OE") (pinfunction "OE_OE") (pintype "bidirectional"))
    )
    (net (code "91") (name "unconnected-(MULTIPLEXER-PadRESET)") (class "Default")
      (node (ref "MULTIPLEXER") (pin "RESET") (pinfunction "RESET_RESET") (pintype "bidirectional"))
    )
    (net (code "92") (name "unconnected-(PCB2-(N{slash}C)-PadN{slash}C)") (class "Default")
      (node (ref "PCB2") (pin "N/C") (pinfunction "(N/C)_N/C") (pintype "bidirectional"))
    )
    (net (code "93") (name "unconnected-(PCB2-0(RX)-Pad0)") (class "Default")
      (node (ref "PCB2") (pin "0") (pinfunction "0(RX)_0") (pintype "bidirectional"))
    )
    (net (code "94") (name "unconnected-(PCB2-1(TX)-Pad1)") (class "Default")
      (node (ref "PCB2") (pin "1") (pinfunction "1(TX)_1") (pintype "bidirectional"))
    )
    (net (code "95") (name "unconnected-(PCB2-IOREF-PadI{slash}OREF)") (class "Default")
      (node (ref "PCB2") (pin "I/OREF") (pinfunction "IOREF_I/OREF") (pintype "bidirectional"))
    )
    (net (code "96") (name "unconnected-(PCB2-Pad8)") (class "Default")
      (node (ref "PCB2") (pin "8") (pinfunction "8_8") (pintype "bidirectional"))
    )
    (net (code "97") (name "unconnected-(PCB2-Pad9)") (class "Default")
      (node (ref "PCB2") (pin "9") (pinfunction "9_9") (pintype "bidirectional"))
    )
    (net (code "98") (name "unconnected-(PCB2-Pad10)") (class "Default")
      (node (ref "PCB2") (pin "10") (pinfunction "10_10") (pintype "bidirectional"))
    )
    (net (code "99") (name "unconnected-(PCB2-Pad11)") (class "Default")
      (node (ref "PCB2") (pin "11") (pinfunction "11_11") (pintype "bidirectional"))
    )
    (net (code "100") (name "unconnected-(PCB2-Pad12)") (class "Default")
      (node (ref "PCB2") (pin "12") (pinfunction "12_12") (pintype "bidirectional"))
    )
    (net (code "101") (name "unconnected-(PCB2-Pad13)") (class "Default")
      (node (ref "PCB2") (pin "13") (pinfunction "13_13") (pintype "bidirectional"))
    )
    (net (code "102") (name "unconnected-(PCB2-Pad22)") (class "Default")
      (node (ref "PCB2") (pin "22") (pinfunction "22_22") (pintype "bidirectional"))
    )
    (net (code "103") (name "unconnected-(PCB2-Pad23)") (class "Default")
      (node (ref "PCB2") (pin "23") (pinfunction "23_23") (pintype "bidirectional"))
    )
    (net (code "104") (name "unconnected-(PCB2-Pad24)") (class "Default")
      (node (ref "PCB2") (pin "24") (pinfunction "24_24") (pintype "bidirectional"))
    )
    (net (code "105") (name "unconnected-(PCB2-Pad25)") (class "Default")
      (node (ref "PCB2") (pin "25") (pinfunction "25_25") (pintype "bidirectional"))
    )
    (net (code "106") (name "unconnected-(PCB2-Pad26)") (class "Default")
      (node (ref "PCB2") (pin "26") (pinfunction "26_26") (pintype "bidirectional"))
    )
    (net (code "107") (name "unconnected-(PCB2-Pad27)") (class "Default")
      (node (ref "PCB2") (pin "27") (pinfunction "27_27") (pintype "bidirectional"))
    )
    (net (code "108") (name "unconnected-(PCB2-Pad28)") (class "Default")
      (node (ref "PCB2") (pin "28") (pinfunction "28_28") (pintype "bidirectional"))
    )
    (net (code "109") (name "unconnected-(PCB2-Pad29)") (class "Default")
      (node (ref "PCB2") (pin "29") (pinfunction "29_29") (pintype "bidirectional"))
    )
    (net (code "110") (name "unconnected-(PCB2-Pad30)") (class "Default")
      (node (ref "PCB2") (pin "30") (pinfunction "30_30") (pintype "bidirectional"))
    )
    (net (code "111") (name "unconnected-(PCB2-Pad44)") (class "Default")
      (node (ref "PCB2") (pin "44") (pinfunction "44_44") (pintype "bidirectional"))
    )
    (net (code "112") (name "unconnected-(PCB2-Pad45)") (class "Default")
      (node (ref "PCB2") (pin "45") (pinfunction "45_45") (pintype "bidirectional"))
    )
    (net (code "113") (name "unconnected-(PCB2-Pad53)") (class "Default")
      (node (ref "PCB2") (pin "53") (pinfunction "53_53") (pintype "bidirectional"))
    )
    (net (code "114") (name "unconnected-(PCB2-PadA2)") (class "Default")
      (node (ref "PCB2") (pin "A2") (pinfunction "A2_A2") (pintype "bidirectional"))
    )
    (net (code "115") (name "unconnected-(PCB2-PadA3)") (class "Default")
      (node (ref "PCB2") (pin "A3") (pinfunction "A3_A3") (pintype "bidirectional"))
    )
    (net (code "116") (name "unconnected-(PCB2-PadA4)") (class "Default")
      (node (ref "PCB2") (pin "A4") (pinfunction "A4_A4") (pintype "bidirectional"))
    )
    (net (code "117") (name "unconnected-(PCB2-PadA5)") (class "Default")
      (node (ref "PCB2") (pin "A5") (pinfunction "A5_A5") (pintype "bidirectional"))
    )
    (net (code "118") (name "unconnected-(PCB2-PadA6)") (class "Default")
      (node (ref "PCB2") (pin "A6") (pinfunction "A6_A6") (pintype "bidirectional"))
    )
    (net (code "119") (name "unconnected-(PCB2-PadA7)") (class "Default")
      (node (ref "PCB2") (pin "A7") (pinfunction "A7_A7") (pintype "bidirectional"))
    )
    (net (code "120") (name "unconnected-(PCB2-PadA8)") (class "Default")
      (node (ref "PCB2") (pin "A8") (pinfunction "A8_A8") (pintype "bidirectional"))
    )
    (net (code "121") (name "unconnected-(PCB2-PadA9)") (class "Default")
      (node (ref "PCB2") (pin "A9") (pinfunction "A9_A9") (pintype "bidirectional"))
    )
    (net (code "122") (name "unconnected-(PCB2-PadA10)") (class "Default")
      (node (ref "PCB2") (pin "A10") (pinfunction "A10_A10") (pintype "bidirectional"))
    )
    (net (code "123") (name "unconnected-(PCB2-PadA11)") (class "Default")
      (node (ref "PCB2") (pin "A11") (pinfunction "A11_A11") (pintype "bidirectional"))
    )
    (net (code "124") (name "unconnected-(PCB2-PadA12)") (class "Default")
      (node (ref "PCB2") (pin "A12") (pinfunction "A12_A12") (pintype "bidirectional"))
    )
    (net (code "125") (name "unconnected-(PCB2-PadA13)") (class "Default")
      (node (ref "PCB2") (pin "A13") (pinfunction "A13_A13") (pintype "bidirectional"))
    )
    (net (code "126") (name "unconnected-(PCB2-PadA14)") (class "Default")
      (node (ref "PCB2") (pin "A14") (pinfunction "A14_A14") (pintype "bidirectional"))
    )
    (net (code "127") (name "unconnected-(PCB2-PadA15)") (class "Default")
      (node (ref "PCB2") (pin "A15") (pinfunction "A15_A15") (pintype "bidirectional"))
    )
    (net (code "128") (name "unconnected-(PCB2-PadAREF)") (class "Default")
      (node (ref "PCB2") (pin "AREF") (pinfunction "AREF_AREF") (pintype "bidirectional"))
    )
    (net (code "129") (name "unconnected-(PCB2-PadRESET)") (class "Default")
      (node (ref "PCB2") (pin "RESET") (pinfunction "RESET_RESET") (pintype "bidirectional"))
    )
    (net (code "130") (name "unconnected-(PCB2-PadSCL1)") (class "Default")
      (node (ref "PCB2") (pin "SCL1") (pinfunction "SCL1_SCL1") (pintype "bidirectional"))
    )
    (net (code "131") (name "unconnected-(PCB2-PadSDA1)") (class "Default")
      (node (ref "PCB2") (pin "SDA1") (pinfunction "SDA1_SDA1") (pintype "bidirectional"))
    )
    (net (code "132") (name "unconnected-(XBEE-AD0{slash}DIO0-Pad20)") (class "Default")
      (node (ref "XBEE") (pin "20") (pinfunction "AD0/DIO0_20") (pintype "bidirectional"))
    )
    (net (code "133") (name "unconnected-(XBEE-AD1{slash}DIO1-Pad19)") (class "Default")
      (node (ref "XBEE") (pin "19") (pinfunction "AD1/DIO1_19") (pintype "bidirectional"))
    )
    (net (code "134") (name "unconnected-(XBEE-AD2{slash}DIO2-Pad18)") (class "Default")
      (node (ref "XBEE") (pin "18") (pinfunction "AD2/DIO2_18") (pintype "bidirectional"))
    )
    (net (code "135") (name "unconnected-(XBEE-AD3{slash}DIO3-Pad17)") (class "Default")
      (node (ref "XBEE") (pin "17") (pinfunction "AD3/DIO3_17") (pintype "bidirectional"))
    )
    (net (code "136") (name "unconnected-(XBEE-AD4{slash}DIO4-Pad11)") (class "Default")
      (node (ref "XBEE") (pin "11") (pinfunction "AD4/DIO4_11") (pintype "bidirectional"))
    )
    (net (code "137") (name "unconnected-(XBEE-ASC{slash}AD5{slash}DIO5-Pad15)") (class "Default")
      (node (ref "XBEE") (pin "15") (pinfunction "ASC/AD5/DIO5_15") (pintype "bidirectional"))
    )
    (net (code "138") (name "unconnected-(XBEE-CTS{slash}DIO7-Pad12)") (class "Default")
      (node (ref "XBEE") (pin "12") (pinfunction "CTS/DIO7_12") (pintype "bidirectional"))
    )
    (net (code "139") (name "unconnected-(XBEE-DO8-Pad4)") (class "Default")
      (node (ref "XBEE") (pin "4") (pinfunction "DO8_4") (pintype "output"))
    )
    (net (code "140") (name "unconnected-(XBEE-DTR{slash}DI8-Pad9)") (class "Default")
      (node (ref "XBEE") (pin "9") (pinfunction "DTR/DI8_9") (pintype "input"))
    )
    (net (code "141") (name "unconnected-(XBEE-ON{slash}SLEEP-Pad13)") (class "Default")
      (node (ref "XBEE") (pin "13") (pinfunction "ON/SLEEP_13") (pintype "output"))
    )
    (net (code "142") (name "unconnected-(XBEE-PWM0{slash}RSSI-Pad6)") (class "Default")
      (node (ref "XBEE") (pin "6") (pinfunction "PWM0/RSSI_6") (pintype "output"))
    )
    (net (code "143") (name "unconnected-(XBEE-PWM1-Pad7)") (class "Default")
      (node (ref "XBEE") (pin "7") (pinfunction "PWM1_7") (pintype "output"))
    )
    (net (code "144") (name "unconnected-(XBEE-RESERVED-Pad8)") (class "Default")
      (node (ref "XBEE") (pin "8") (pinfunction "RESERVED_8") (pintype "no_connect"))
    )
    (net (code "145") (name "unconnected-(XBEE-RESET-Pad5)") (class "Default")
      (node (ref "XBEE") (pin "5") (pinfunction "RESET_5") (pintype "input"))
    )
    (net (code "146") (name "unconnected-(XBEE-RTS{slash}AD6{slash}DIO6-Pad16)") (class "Default")
      (node (ref "XBEE") (pin "16") (pinfunction "RTS/AD6/DIO6_16") (pintype "bidirectional"))
    )
    (net (code "147") (name "unconnected-(XBEE-VREF-Pad14)") (class "Default")
      (node (ref "XBEE") (pin "14") (pinfunction "VREF_14") (pintype "input"))
    )
  )
)
